# Sheet1.net
KiCad netlist of a schematic drawn in Altium Designer
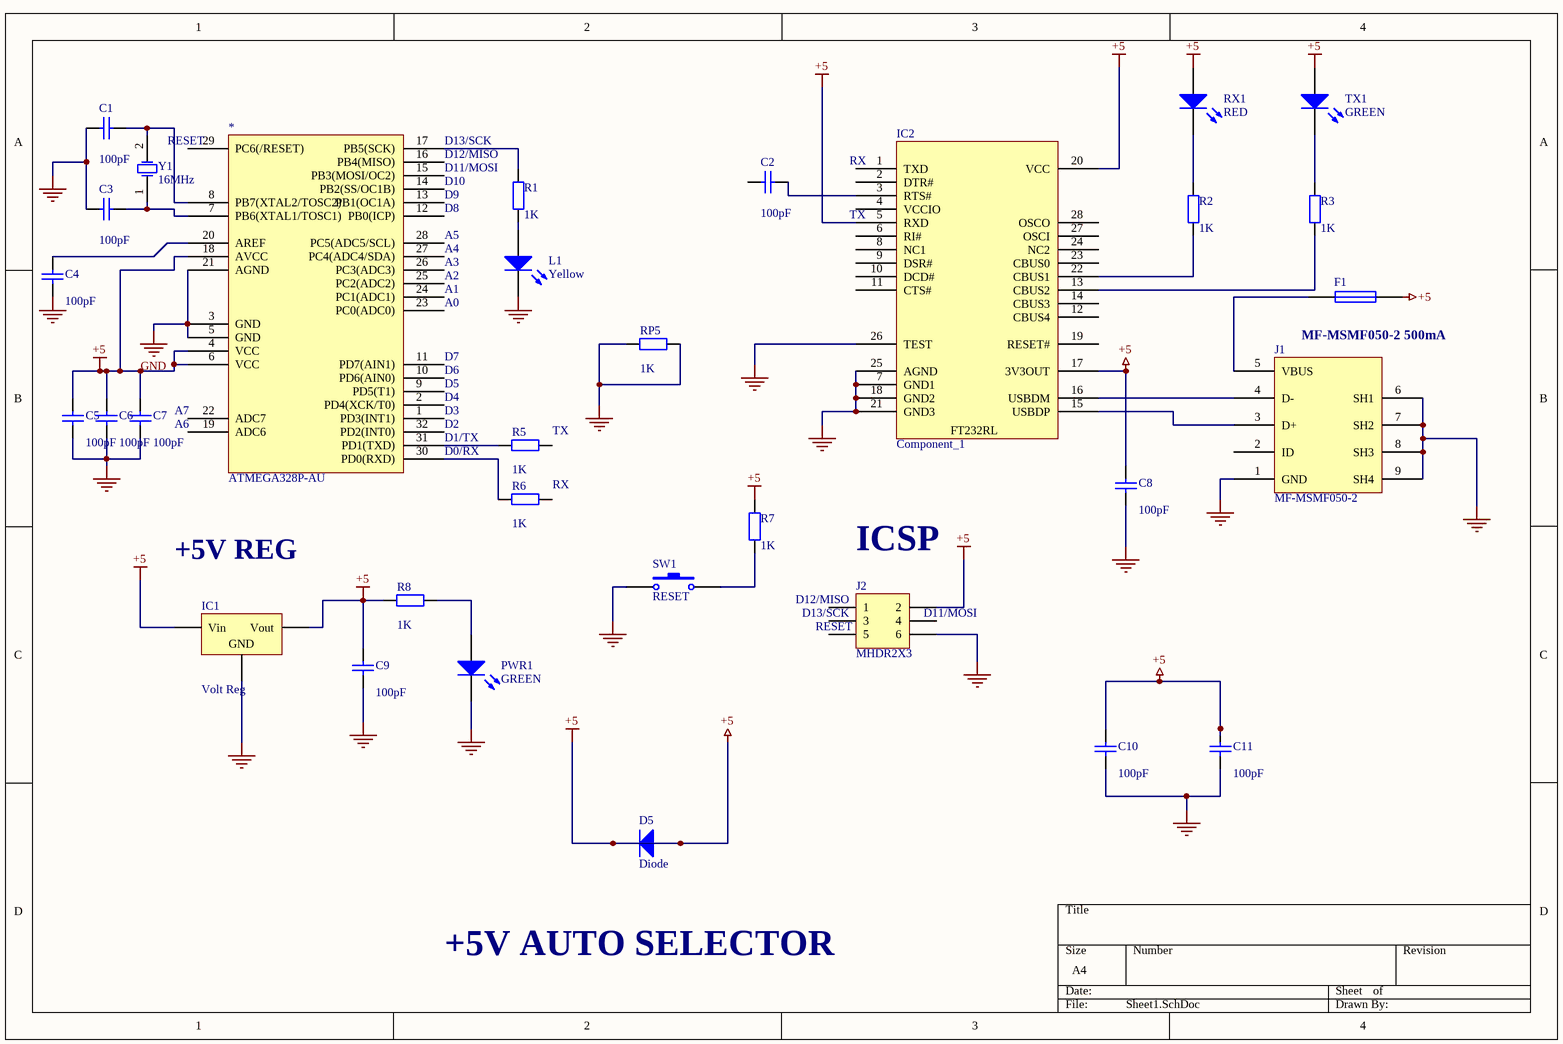
[diagram p0: Sheet1.SchDoc]

(export (version "E")
  (design (tool "Eeschema 10.0.6"))
  (components
    (comp (ref "*")
      (value "ATMEGA328P-AU")
      (footprint "SOIC127P980X95_HS-33N")
      (libsource (lib "Schlib1") (part "ATMEGA328P-AU"))
    )
    (comp (ref "C1")
      (value "100pF")
      (footprint "RAD-0.3")
      (description "Capacitor")
      (fields (field (name "Comment") "Cap") (field (name "PUBLISHER") "Altium Limited"))
      (libsource (lib "Miscellaneous Devices") (part "Cap"))
    )
    (comp (ref "C2")
      (value "100pF")
      (footprint "RAD-0.3")
      (description "Capacitor")
      (fields (field (name "Comment") "Cap") (field (name "PUBLISHER") "Altium Limited"))
      (libsource (lib "Miscellaneous Devices") (part "Cap"))
    )
    (comp (ref "C3")
      (value "100pF")
      (footprint "RAD-0.3")
      (description "Capacitor")
      (fields (field (name "Comment") "Cap") (field (name "PUBLISHER") "Altium Limited"))
      (libsource (lib "Miscellaneous Devices") (part "Cap"))
    )
    (comp (ref "C4")
      (value "100pF")
      (footprint "RAD-0.3")
      (description "Capacitor")
      (fields (field (name "Comment") "Cap") (field (name "PUBLISHER") "Altium Limited"))
      (libsource (lib "Miscellaneous Devices") (part "Cap"))
    )
    (comp (ref "C5")
      (value "100pF")
      (footprint "RAD-0.3")
      (description "Capacitor")
      (fields (field (name "Comment") "Cap") (field (name "PUBLISHER") "Altium Limited"))
      (libsource (lib "Miscellaneous Devices") (part "Cap"))
    )
    (comp (ref "C6")
      (value "100pF")
      (footprint "RAD-0.3")
      (description "Capacitor")
      (fields (field (name "Comment") "Cap") (field (name "PUBLISHER") "Altium Limited"))
      (libsource (lib "Miscellaneous Devices") (part "Cap"))
    )
    (comp (ref "C7")
      (value "100pF")
      (footprint "RAD-0.3")
      (description "Capacitor")
      (fields (field (name "Comment") "Cap") (field (name "PUBLISHER") "Altium Limited"))
      (libsource (lib "Miscellaneous Devices") (part "Cap"))
    )
    (comp (ref "C8")
      (value "100pF")
      (footprint "RAD-0.3")
      (description "Capacitor")
      (fields (field (name "Comment") "Cap") (field (name "PUBLISHER") "Altium Limited"))
      (libsource (lib "Miscellaneous Devices") (part "Cap"))
    )
    (comp (ref "C9")
      (value "100pF")
      (footprint "RAD-0.3")
      (description "Capacitor")
      (fields (field (name "Comment") "Cap") (field (name "PUBLISHER") "Altium Limited"))
      (libsource (lib "Miscellaneous Devices") (part "Cap"))
    )
    (comp (ref "C10")
      (value "100pF")
      (footprint "RAD-0.3")
      (description "Capacitor")
      (fields (field (name "Comment") "Cap") (field (name "PUBLISHER") "Altium Limited"))
      (libsource (lib "Miscellaneous Devices") (part "Cap"))
    )
    (comp (ref "C11")
      (value "100pF")
      (footprint "RAD-0.3")
      (description "Capacitor")
      (fields (field (name "Comment") "Cap") (field (name "PUBLISHER") "Altium Limited"))
      (libsource (lib "Miscellaneous Devices") (part "Cap"))
    )
    (comp (ref "D5")
      (value "Diode")
      (footprint "SMC")
      (description "Default Diode")
      (fields (field (name "PUBLISHER") "Altium Limited"))
      (libsource (lib "Miscellaneous Devices") (part "Diode"))
    )
    (comp (ref "F1")
      (value "Fuse 1")
      (footprint "PIN-W2/E2.8")
      (description "Fuse")
      (fields (field (name "PUBLISHER") "Altium Limited"))
      (libsource (lib "Miscellaneous Devices") (part "Fuse 1"))
    )
    (comp (ref "IC1")
      (value "Volt Reg")
      (footprint "D2PAK_N")
      (description "Voltage Regulator")
      (fields (field (name "PUBLISHER") "Altium Limited"))
      (libsource (lib "Miscellaneous Devices") (part "Volt Reg"))
    )
    (comp (ref "IC2")
      (value "Component_1")
      (footprint "SOIC127P980X95_HS-29N")
      (libsource (lib "Schlib1") (part "Component_1"))
    )
    (comp (ref "J1")
      (value "MF-MSMF050-2")
      (footprint "SOIC127P980X95_HS-10N")
      (libsource (lib "Schlib3") (part "MF-MSMF050-2"))
    )
    (comp (ref "J2")
      (value "MHDR2X3")
      (footprint "MHDR2X3")
      (description "Header, 3-Pin, Dual row")
      (fields (field (name "PUBLISHER") "Altium Limited"))
      (libsource (lib "Miscellaneous Connectors") (part "MHDR2X3"))
    )
    (comp (ref "L1")
      (value "Yellow")
      (footprint "3.2X1.6X1.1")
      (description "Typical RED, GREEN, YELLOW, AMBER GaAs LED")
      (fields (field (name "PUBLISHER") "Altium Limited"))
      (libsource (lib "Miscellaneous Devices") (part "LED2"))
    )
    (comp (ref "PWR1")
      (value "GREEN")
      (footprint "3.2X1.6X1.1")
      (description "Typical RED, GREEN, YELLOW, AMBER GaAs LED")
      (fields (field (name "PUBLISHER") "Altium Limited"))
      (libsource (lib "Miscellaneous Devices") (part "LED2"))
    )
    (comp (ref "R1")
      (value "1K")
      (footprint "AXIAL-0.4")
      (description "Resistor")
      (fields (field (name "Comment") "Res2") (field (name "PUBLISHER") "Altium Limited"))
      (libsource (lib "") (part "Res2_1"))
    )
    (comp (ref "R2")
      (value "1K")
      (footprint "AXIAL-0.4")
      (description "Resistor")
      (fields (field (name "Comment") "Res2") (field (name "PUBLISHER") "Altium Limited"))
      (libsource (lib "") (part "Res2_1"))
    )
    (comp (ref "R3")
      (value "1K")
      (footprint "AXIAL-0.4")
      (description "Resistor")
      (fields (field (name "Comment") "Res2") (field (name "PUBLISHER") "Altium Limited"))
      (libsource (lib "") (part "Res2_1"))
    )
    (comp (ref "R5")
      (value "1K")
      (footprint "AXIAL-0.4")
      (description "Resistor")
      (fields (field (name "Comment") "Res2") (field (name "PUBLISHER") "Altium Limited"))
      (libsource (lib "Miscellaneous Devices") (part "Res2"))
    )
    (comp (ref "R6")
      (value "1K")
      (footprint "AXIAL-0.4")
      (description "Resistor")
      (fields (field (name "Comment") "Res2") (field (name "PUBLISHER") "Altium Limited"))
      (libsource (lib "Miscellaneous Devices") (part "Res2"))
    )
    (comp (ref "R7")
      (value "1K")
      (footprint "AXIAL-0.4")
      (description "Resistor")
      (fields (field (name "Comment") "Res2") (field (name "PUBLISHER") "Altium Limited"))
      (libsource (lib "") (part "Res2_1"))
    )
    (comp (ref "R8")
      (value "1K")
      (footprint "AXIAL-0.4")
      (description "Resistor")
      (fields (field (name "Comment") "Res2") (field (name "PUBLISHER") "Altium Limited"))
      (libsource (lib "") (part "Res2_2"))
    )
    (comp (ref "RP5")
      (value "1K")
      (footprint "AXIAL-0.4")
      (description "Resistor")
      (fields (field (name "Comment") "Res2") (field (name "PUBLISHER") "Altium Limited"))
      (libsource (lib "Miscellaneous Devices") (part "Res2"))
    )
    (comp (ref "RX1")
      (value "RED")
      (footprint "3.2X1.6X1.1")
      (description "Typical RED, GREEN, YELLOW, AMBER GaAs LED")
      (fields (field (name "PUBLISHER") "Altium Limited"))
      (libsource (lib "Miscellaneous Devices") (part "LED2"))
    )
    (comp (ref "SW1")
      (value "RESET")
      (footprint "SPST-2")
      (description "Switch")
      (fields (field (name "PUBLISHER") "Altium Limited"))
      (libsource (lib "Miscellaneous Devices") (part "SW-PB"))
    )
    (comp (ref "TX1")
      (value "GREEN")
      (footprint "3.2X1.6X1.1")
      (description "Typical RED, GREEN, YELLOW, AMBER GaAs LED")
      (fields (field (name "PUBLISHER") "Altium Limited"))
      (libsource (lib "Miscellaneous Devices") (part "LED2"))
    )
    (comp (ref "Y1")
      (value "16MHz")
      (footprint "R38")
      (description "Crystal Oscillator")
      (fields (field (name "PUBLISHER") "Altium Limited"))
      (libsource (lib "Miscellaneous Devices") (part "XTAL"))
    )
  )
  (nets
    (net (code "1") (name "+5") (class "Default")
      (node (ref "*") (pin "18") (pinfunction "AVCC_18") (pintype "passive"))
      (node (ref "*") (pin "4") (pinfunction "VCC_4") (pintype "power_in"))
      (node (ref "*") (pin "6") (pinfunction "VCC_6") (pintype "power_in"))
      (node (ref "C10") (pin "2") (pinfunction "2_2") (pintype "passive"))
      (node (ref "C11") (pin "2") (pinfunction "2_2") (pintype "passive"))
      (node (ref "C5") (pin "2") (pinfunction "2_2") (pintype "passive"))
      (node (ref "C6") (pin "2") (pinfunction "2_2") (pintype "passive"))
      (node (ref "C7") (pin "2") (pinfunction "2_2") (pintype "passive"))
      (node (ref "C8") (pin "2") (pinfunction "2_2") (pintype "passive"))
      (node (ref "C9") (pin "2") (pinfunction "2_2") (pintype "passive"))
      (node (ref "D5") (pin "1") (pinfunction "A_1") (pintype "passive"))
      (node (ref "D5") (pin "2") (pinfunction "K_2") (pintype "passive"))
      (node (ref "F1") (pin "2") (pinfunction "2_2") (pintype "passive"))
      (node (ref "IC1") (pin "1") (pinfunction "Vin_1") (pintype "passive"))
      (node (ref "IC1") (pin "3") (pinfunction "Vout_3") (pintype "passive"))
      (node (ref "IC2") (pin "17") (pinfunction "3V3OUT_17") (pintype "passive"))
      (node (ref "IC2") (pin "20") (pinfunction "VCC_20") (pintype "passive"))
      (node (ref "IC2") (pin "5") (pinfunction "RXD_5") (pintype "passive"))
      (node (ref "J2") (pin "2") (pinfunction "2_2") (pintype "passive"))
      (node (ref "R7") (pin "2") (pinfunction "2_2") (pintype "passive"))
      (node (ref "R8") (pin "1") (pinfunction "1_1") (pintype "passive"))
      (node (ref "RX1") (pin "1") (pinfunction "A_1") (pintype "passive"))
      (node (ref "TX1") (pin "1") (pinfunction "A_1") (pintype "passive"))
    )
    (net (code "2") (name "GND") (class "Default")
      (node (ref "*") (pin "21") (pinfunction "AGND_21") (pintype "passive"))
      (node (ref "*") (pin "3") (pinfunction "GND_3") (pintype "passive"))
      (node (ref "*") (pin "5") (pinfunction "GND_5") (pintype "passive"))
      (node (ref "C1") (pin "1") (pinfunction "1_1") (pintype "passive"))
      (node (ref "C10") (pin "1") (pinfunction "1_1") (pintype "passive"))
      (node (ref "C11") (pin "1") (pinfunction "1_1") (pintype "passive"))
      (node (ref "C3") (pin "1") (pinfunction "1_1") (pintype "passive"))
      (node (ref "C4") (pin "1") (pinfunction "1_1") (pintype "passive"))
      (node (ref "C5") (pin "1") (pinfunction "1_1") (pintype "passive"))
      (node (ref "C6") (pin "1") (pinfunction "1_1") (pintype "passive"))
      (node (ref "C7") (pin "1") (pinfunction "1_1") (pintype "passive"))
      (node (ref "C8") (pin "1") (pinfunction "1_1") (pintype "passive"))
      (node (ref "C9") (pin "1") (pinfunction "1_1") (pintype "passive"))
      (node (ref "IC1") (pin "2") (pinfunction "GND_2") (pintype "passive"))
      (node (ref "IC2") (pin "18") (pinfunction "GND2_18") (pintype "passive"))
      (node (ref "IC2") (pin "21") (pinfunction "GND3_21") (pintype "passive"))
      (node (ref "IC2") (pin "25") (pinfunction "AGND_25") (pintype "passive"))
      (node (ref "IC2") (pin "26") (pinfunction "TEST_26") (pintype "passive"))
      (node (ref "IC2") (pin "7") (pinfunction "GND1_7") (pintype "passive"))
      (node (ref "J1") (pin "1") (pinfunction "GND_1") (pintype "passive"))
      (node (ref "J1") (pin "6") (pinfunction "SH1_6") (pintype "passive"))
      (node (ref "J1") (pin "7") (pinfunction "SH2_7") (pintype "passive"))
      (node (ref "J1") (pin "8") (pinfunction "SH3_8") (pintype "passive"))
      (node (ref "J1") (pin "9") (pinfunction "SH4_9") (pintype "passive"))
      (node (ref "J2") (pin "6") (pinfunction "6_6") (pintype "passive"))
      (node (ref "L1") (pin "2") (pinfunction "K_2") (pintype "passive"))
      (node (ref "PWR1") (pin "2") (pinfunction "K_2") (pintype "passive"))
      (node (ref "RP5") (pin "1") (pinfunction "1_1") (pintype "passive"))
      (node (ref "RP5") (pin "2") (pinfunction "2_2") (pintype "passive"))
      (node (ref "SW1") (pin "1") (pinfunction "1_1") (pintype "passive"))
    )
    (net (code "3") (name "Net-(*-AREF)") (class "Default")
      (node (ref "*") (pin "20") (pinfunction "AREF_20") (pintype "passive"))
      (node (ref "C4") (pin "2") (pinfunction "2_2") (pintype "passive"))
    )
    (net (code "4") (name "Net-(*-PB5(SCK))") (class "Default")
      (node (ref "*") (pin "17") (pinfunction "PB5(SCK)_17") (pintype "passive"))
      (node (ref "R1") (pin "2") (pinfunction "2_2") (pintype "passive"))
    )
    (net (code "5") (name "Net-(*-PB6(XTAL1{slash}TOSC1))") (class "Default")
      (node (ref "*") (pin "7") (pinfunction "PB6(XTAL1/TOSC1)_7") (pintype "passive"))
      (node (ref "C3") (pin "2") (pinfunction "2_2") (pintype "passive"))
      (node (ref "Y1") (pin "1") (pinfunction "OSC1_1") (pintype "passive"))
    )
    (net (code "6") (name "Net-(*-PB7(XTAL2{slash}TOSC2))") (class "Default")
      (node (ref "*") (pin "8") (pinfunction "PB7(XTAL2/TOSC2)_8") (pintype "passive"))
      (node (ref "C1") (pin "2") (pinfunction "2_2") (pintype "passive"))
      (node (ref "Y1") (pin "2") (pinfunction "OSC2_2") (pintype "passive"))
    )
    (net (code "7") (name "Net-(*-PD0(RXD))") (class "Default")
      (node (ref "*") (pin "30") (pinfunction "PD0(RXD)_30") (pintype "passive"))
      (node (ref "R6") (pin "2") (pinfunction "2_2") (pintype "passive"))
    )
    (net (code "8") (name "Net-(*-PD1(TXD))") (class "Default")
      (node (ref "*") (pin "31") (pinfunction "PD1(TXD)_31") (pintype "passive"))
      (node (ref "R5") (pin "2") (pinfunction "2_2") (pintype "passive"))
    )
    (net (code "9") (name "Net-(IC2-CBUS1)") (class "Default")
      (node (ref "IC2") (pin "22") (pinfunction "CBUS1_22") (pintype "passive"))
      (node (ref "R2") (pin "1") (pinfunction "1_1") (pintype "passive"))
    )
    (net (code "10") (name "Net-(IC2-CBUS2)") (class "Default")
      (node (ref "IC2") (pin "13") (pinfunction "CBUS2_13") (pintype "passive"))
      (node (ref "R3") (pin "1") (pinfunction "1_1") (pintype "passive"))
    )
    (net (code "11") (name "Net-(IC2-RTS#)") (class "Default")
      (node (ref "C2") (pin "2") (pinfunction "2_2") (pintype "passive"))
      (node (ref "IC2") (pin "3") (pinfunction "RTS#_3") (pintype "passive"))
    )
    (net (code "12") (name "Net-(IC2-USBDM)") (class "Default")
      (node (ref "IC2") (pin "16") (pinfunction "USBDM_16") (pintype "passive"))
      (node (ref "J1") (pin "4") (pinfunction "D-_4") (pintype "passive"))
    )
    (net (code "13") (name "Net-(IC2-USBDP)") (class "Default")
      (node (ref "IC2") (pin "15") (pinfunction "USBDP_15") (pintype "passive"))
      (node (ref "J1") (pin "3") (pinfunction "D+_3") (pintype "passive"))
    )
    (net (code "14") (name "Net-(J1-VBUS)") (class "Default")
      (node (ref "F1") (pin "1") (pinfunction "1_1") (pintype "passive"))
      (node (ref "J1") (pin "5") (pinfunction "VBUS_5") (pintype "passive"))
    )
    (net (code "15") (name "Net-(L1-A)") (class "Default")
      (node (ref "L1") (pin "1") (pinfunction "A_1") (pintype "passive"))
      (node (ref "R1") (pin "1") (pinfunction "1_1") (pintype "passive"))
    )
    (net (code "16") (name "Net-(PWR1-A)") (class "Default")
      (node (ref "PWR1") (pin "1") (pinfunction "A_1") (pintype "passive"))
      (node (ref "R8") (pin "2") (pinfunction "2_2") (pintype "passive"))
    )
    (net (code "17") (name "Net-(R7-Pad1)") (class "Default")
      (node (ref "R7") (pin "1") (pinfunction "1_1") (pintype "passive"))
      (node (ref "SW1") (pin "2") (pinfunction "2_2") (pintype "passive"))
    )
    (net (code "18") (name "Net-(RX1-K)") (class "Default")
      (node (ref "R2") (pin "2") (pinfunction "2_2") (pintype "passive"))
      (node (ref "RX1") (pin "2") (pinfunction "K_2") (pintype "passive"))
    )
    (net (code "19") (name "Net-(TX1-K)") (class "Default")
      (node (ref "R3") (pin "2") (pinfunction "2_2") (pintype "passive"))
      (node (ref "TX1") (pin "2") (pinfunction "K_2") (pintype "passive"))
    )
    (net (code "20") (name "unconnected-(*-ADC6-Pad19)") (class "Default")
      (node (ref "*") (pin "19") (pinfunction "ADC6_19") (pintype "passive"))
    )
    (net (code "21") (name "unconnected-(*-ADC7-Pad22)") (class "Default")
      (node (ref "*") (pin "22") (pinfunction "ADC7_22") (pintype "passive"))
    )
    (net (code "22") (name "unconnected-(*-PB0(ICP)-Pad12)") (class "Default")
      (node (ref "*") (pin "12") (pinfunction "PB0(ICP)_12") (pintype "passive"))
    )
    (net (code "23") (name "unconnected-(*-PB1(OC1A)-Pad13)") (class "Default")
      (node (ref "*") (pin "13") (pinfunction "PB1(OC1A)_13") (pintype "passive"))
    )
    (net (code "24") (name "unconnected-(*-PB2(SS{slash}OC1B)-Pad14)") (class "Default")
      (node (ref "*") (pin "14") (pinfunction "PB2(SS/OC1B)_14") (pintype "passive"))
    )
    (net (code "25") (name "unconnected-(*-PB3(MOSI{slash}OC2)-Pad15)") (class "Default")
      (node (ref "*") (pin "15") (pinfunction "PB3(MOSI/OC2)_15") (pintype "passive"))
    )
    (net (code "26") (name "unconnected-(*-PB4(MISO)-Pad16)") (class "Default")
      (node (ref "*") (pin "16") (pinfunction "PB4(MISO)_16") (pintype "passive"))
    )
    (net (code "27") (name "unconnected-(*-PC0(ADC0)-Pad23)") (class "Default")
      (node (ref "*") (pin "23") (pinfunction "PC0(ADC0)_23") (pintype "passive"))
    )
    (net (code "28") (name "unconnected-(*-PC1(ADC1)-Pad24)") (class "Default")
      (node (ref "*") (pin "24") (pinfunction "PC1(ADC1)_24") (pintype "passive"))
    )
    (net (code "29") (name "unconnected-(*-PC2(ADC2)-Pad25)") (class "Default")
      (node (ref "*") (pin "25") (pinfunction "PC2(ADC2)_25") (pintype "passive"))
    )
    (net (code "30") (name "unconnected-(*-PC3(ADC3)-Pad26)") (class "Default")
      (node (ref "*") (pin "26") (pinfunction "PC3(ADC3)_26") (pintype "passive"))
    )
    (net (code "31") (name "unconnected-(*-PC4(ADC4{slash}SDA)-Pad27)") (class "Default")
      (node (ref "*") (pin "27") (pinfunction "PC4(ADC4/SDA)_27") (pintype "passive"))
    )
    (net (code "32") (name "unconnected-(*-PC5(ADC5{slash}SCL)-Pad28)") (class "Default")
      (node (ref "*") (pin "28") (pinfunction "PC5(ADC5/SCL)_28") (pintype "passive"))
    )
    (net (code "33") (name "unconnected-(*-PC6({slash}RESET)-Pad29)") (class "Default")
      (node (ref "*") (pin "29") (pinfunction "PC6(/RESET)_29") (pintype "passive"))
    )
    (net (code "34") (name "unconnected-(*-PD2(INT0)-Pad32)") (class "Default")
      (node (ref "*") (pin "32") (pinfunction "PD2(INT0)_32") (pintype "passive"))
    )
    (net (code "35") (name "unconnected-(*-PD3(INT1)-Pad1)") (class "Default")
      (node (ref "*") (pin "1") (pinfunction "PD3(INT1)_1") (pintype "passive"))
    )
    (net (code "36") (name "unconnected-(*-PD4(XCK{slash}T0)-Pad2)") (class "Default")
      (node (ref "*") (pin "2") (pinfunction "PD4(XCK/T0)_2") (pintype "passive"))
    )
    (net (code "37") (name "unconnected-(*-PD5(T1)-Pad9)") (class "Default")
      (node (ref "*") (pin "9") (pinfunction "PD5(T1)_9") (pintype "passive"))
    )
    (net (code "38") (name "unconnected-(*-PD6(AIN0)-Pad10)") (class "Default")
      (node (ref "*") (pin "10") (pinfunction "PD6(AIN0)_10") (pintype "passive"))
    )
    (net (code "39") (name "unconnected-(*-PD7(AIN1)-Pad11)") (class "Default")
      (node (ref "*") (pin "11") (pinfunction "PD7(AIN1)_11") (pintype "passive"))
    )
    (net (code "40") (name "unconnected-(C2-Pad1)") (class "Default")
      (node (ref "C2") (pin "1") (pinfunction "1_1") (pintype "passive"))
    )
    (net (code "41") (name "unconnected-(IC2-CBUS0-Pad23)") (class "Default")
      (node (ref "IC2") (pin "23") (pinfunction "CBUS0_23") (pintype "passive"))
    )
    (net (code "42") (name "unconnected-(IC2-CBUS3-Pad14)") (class "Default")
      (node (ref "IC2") (pin "14") (pinfunction "CBUS3_14") (pintype "passive"))
    )
    (net (code "43") (name "unconnected-(IC2-CBUS4-Pad12)") (class "Default")
      (node (ref "IC2") (pin "12") (pinfunction "CBUS4_12") (pintype "passive"))
    )
    (net (code "44") (name "unconnected-(IC2-CTS#-Pad11)") (class "Default")
      (node (ref "IC2") (pin "11") (pinfunction "CTS#_11") (pintype "passive"))
    )
    (net (code "45") (name "unconnected-(IC2-DCD#-Pad10)") (class "Default")
      (node (ref "IC2") (pin "10") (pinfunction "DCD#_10") (pintype "passive"))
    )
    (net (code "46") (name "unconnected-(IC2-DSR#-Pad9)") (class "Default")
      (node (ref "IC2") (pin "9") (pinfunction "DSR#_9") (pintype "passive"))
    )
    (net (code "47") (name "unconnected-(IC2-DTR#-Pad2)") (class "Default")
      (node (ref "IC2") (pin "2") (pinfunction "DTR#_2") (pintype "passive"))
    )
    (net (code "48") (name "unconnected-(IC2-NC1-Pad8)") (class "Default")
      (node (ref "IC2") (pin "8") (pinfunction "NC1_8") (pintype "passive"))
    )
    (net (code "49") (name "unconnected-(IC2-NC2-Pad24)") (class "Default")
      (node (ref "IC2") (pin "24") (pinfunction "NC2_24") (pintype "passive"))
    )
    (net (code "50") (name "unconnected-(IC2-OSCI-Pad27)") (class "Default")
      (node (ref "IC2") (pin "27") (pinfunction "OSCI_27") (pintype "passive"))
    )
    (net (code "51") (name "unconnected-(IC2-OSCO-Pad28)") (class "Default")
      (node (ref "IC2") (pin "28") (pinfunction "OSCO_28") (pintype "passive"))
    )
    (net (code "52") (name "unconnected-(IC2-RESET#-Pad19)") (class "Default")
      (node (ref "IC2") (pin "19") (pinfunction "RESET#_19") (pintype "passive"))
    )
    (net (code "53") (name "unconnected-(IC2-RI#-Pad6)") (class "Default")
      (node (ref "IC2") (pin "6") (pinfunction "RI#_6") (pintype "passive"))
    )
    (net (code "54") (name "unconnected-(IC2-TXD-Pad1)") (class "Default")
      (node (ref "IC2") (pin "1") (pinfunction "TXD_1") (pintype "passive"))
    )
    (net (code "55") (name "unconnected-(IC2-VCCIO-Pad4)") (class "Default")
      (node (ref "IC2") (pin "4") (pinfunction "VCCIO_4") (pintype "passive"))
    )
    (net (code "56") (name "unconnected-(J1-ID-Pad2)") (class "Default")
      (node (ref "J1") (pin "2") (pinfunction "ID_2") (pintype "passive"))
    )
    (net (code "57") (name "unconnected-(J2-Pad1)") (class "Default")
      (node (ref "J2") (pin "1") (pinfunction "1_1") (pintype "passive"))
    )
    (net (code "58") (name "unconnected-(J2-Pad3)") (class "Default")
      (node (ref "J2") (pin "3") (pinfunction "3_3") (pintype "passive"))
    )
    (net (code "59") (name "unconnected-(J2-Pad4)") (class "Default")
      (node (ref "J2") (pin "4") (pinfunction "4_4") (pintype "passive"))
    )
    (net (code "60") (name "unconnected-(J2-Pad5)") (class "Default")
      (node (ref "J2") (pin "5") (pinfunction "5_5") (pintype "passive"))
    )
    (net (code "61") (name "unconnected-(R5-Pad1)") (class "Default")
      (node (ref "R5") (pin "1") (pinfunction "1_1") (pintype "passive"))
    )
    (net (code "62") (name "unconnected-(R6-Pad1)") (class "Default")
      (node (ref "R6") (pin "1") (pinfunction "1_1") (pintype "passive"))
    )
  )
)
